# GSM_Link_12_SIM900A.net
KiCad netlist of a schematic drawn in Altium Designer
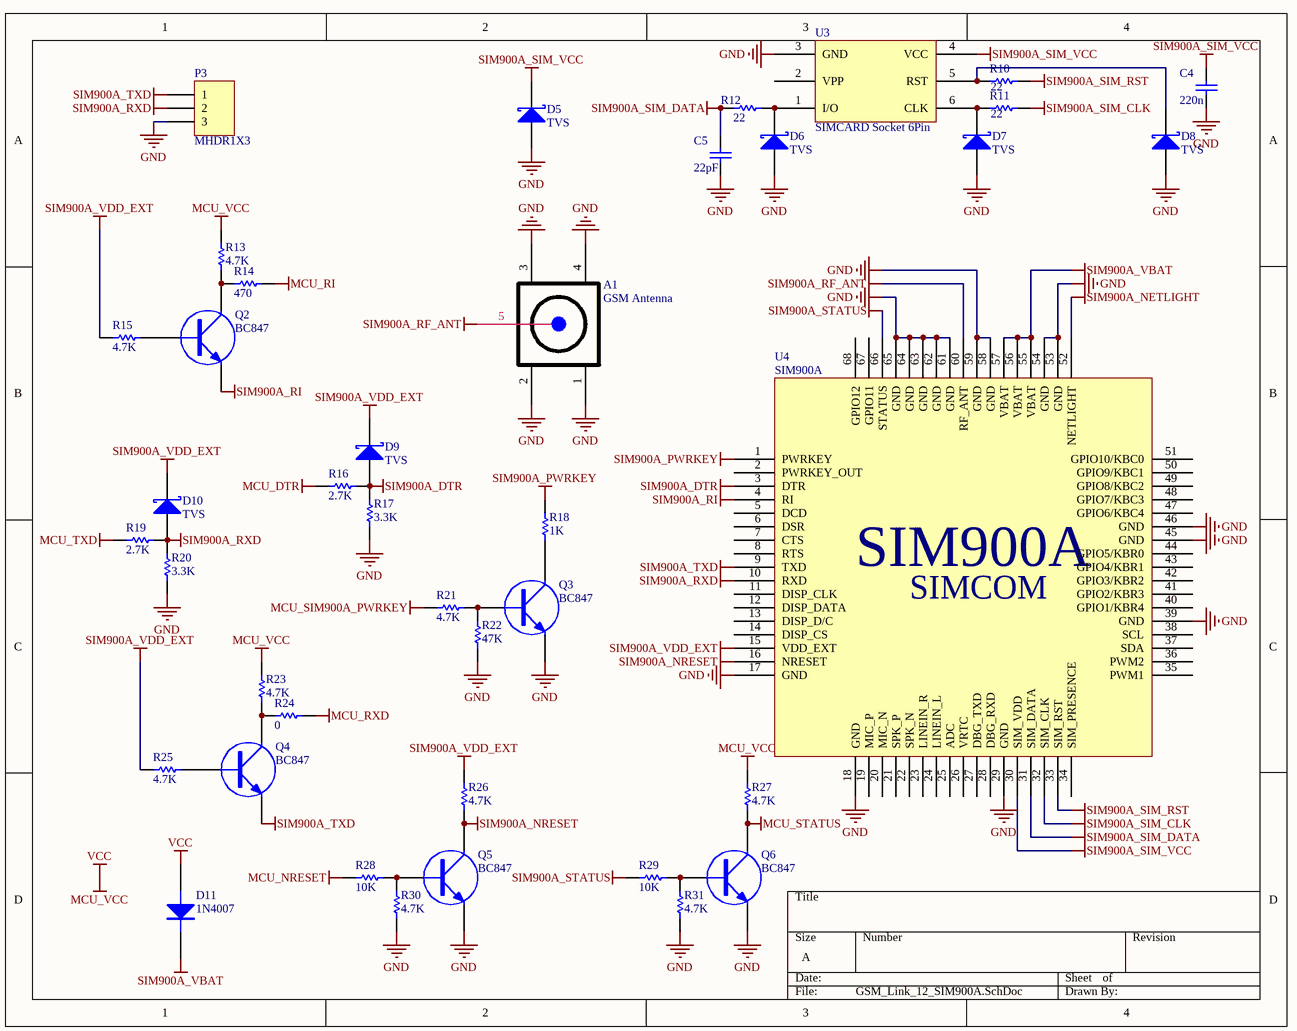
[diagram p0: GSM_Link_12_SIM900A.SchDoc]

(export (version "E")
  (design (tool "Eeschema 10.0.6"))
  (components
    (comp (ref "A1")
      (value "GSM Antenna")
      (footprint "SMA Right Female")
      (libsource (lib "BNB_Altium_LIB_004") (part "SMA KWE-F"))
    )
    (comp (ref "C4")
      (value "220n")
      (footprint "0805_smd")
      (description "Capacitor")
      (fields (field (name "PUBLISHER") "Altium Limited"))
      (libsource (lib "Miscellaneous Devices") (part "Cap"))
    )
    (comp (ref "C5")
      (value "22pF")
      (footprint "0805_smd")
      (description "Capacitor")
      (fields (field (name "PUBLISHER") "Altium Limited"))
      (libsource (lib "Miscellaneous Devices") (part "Cap"))
    )
    (comp (ref "D5")
      (value "TVS")
      (footprint "7227_SMD")
      (description "Schottky Diode")
      (fields (field (name "PUBLISHER") "Altium Limited"))
      (libsource (lib "Miscellaneous Devices") (part "D Schottky"))
    )
    (comp (ref "D6")
      (value "TVS")
      (footprint "7227_SMD")
      (description "Schottky Diode")
      (fields (field (name "PUBLISHER") "Altium Limited"))
      (libsource (lib "Miscellaneous Devices") (part "D Schottky"))
    )
    (comp (ref "D7")
      (value "TVS")
      (footprint "7227_SMD")
      (description "Schottky Diode")
      (fields (field (name "PUBLISHER") "Altium Limited"))
      (libsource (lib "Miscellaneous Devices") (part "D Schottky"))
    )
    (comp (ref "D8")
      (value "TVS")
      (footprint "7227_SMD")
      (description "Schottky Diode")
      (fields (field (name "PUBLISHER") "Altium Limited"))
      (libsource (lib "Miscellaneous Devices") (part "D Schottky"))
    )
    (comp (ref "D9")
      (value "TVS")
      (footprint "7227_SMD")
      (description "Schottky Diode")
      (fields (field (name "PUBLISHER") "Altium Limited"))
      (libsource (lib "Miscellaneous Devices") (part "D Schottky"))
    )
    (comp (ref "D10")
      (value "TVS")
      (footprint "7227_SMD")
      (description "Schottky Diode")
      (fields (field (name "PUBLISHER") "Altium Limited"))
      (libsource (lib "Miscellaneous Devices") (part "D Schottky"))
    )
    (comp (ref "D11")
      (value "1N4007")
      (footprint "7227_SMD")
      (description "Diode")
      (libsource (lib "*") (part "DIODE"))
    )
    (comp (ref "P3")
      (value "MHDR1X3")
      (footprint "CON3_XH")
      (description "Header, 3-Pin")
      (fields (field (name "PUBLISHER") "Altium Limited"))
      (libsource (lib "Miscellaneous Connectors") (part "MHDR1X3"))
    )
    (comp (ref "Q2") (value "BC847") (footprint "SOT23_SMD") (libsource (lib "Schlib75") (part "BC547")))
    (comp (ref "Q3") (value "BC847") (footprint "SOT23_SMD") (libsource (lib "Schlib75") (part "BC547")))
    (comp (ref "Q4") (value "BC847") (footprint "SOT23_SMD") (libsource (lib "Schlib75") (part "BC547")))
    (comp (ref "Q5") (value "BC847") (footprint "SOT23_SMD") (libsource (lib "Schlib75") (part "BC547")))
    (comp (ref "Q6") (value "BC847") (footprint "SOT23_SMD") (libsource (lib "Schlib75") (part "BC547")))
    (comp (ref "R10")
      (value "22")
      (footprint "0805_SMD")
      (description "Resistor")
      (fields (field (name "PUBLISHER") "Altium Limited"))
      (libsource (lib "Miscellaneous Devices") (part "Res1"))
    )
    (comp (ref "R11")
      (value "22")
      (footprint "0805_SMD")
      (description "Resistor")
      (fields (field (name "PUBLISHER") "Altium Limited"))
      (libsource (lib "Miscellaneous Devices") (part "Res1"))
    )
    (comp (ref "R12")
      (value "22")
      (footprint "1206_SMD")
      (description "Resistor")
      (fields (field (name "PUBLISHER") "Altium Limited"))
      (libsource (lib "Miscellaneous Devices") (part "Res1"))
    )
    (comp (ref "R13")
      (value "4.7K")
      (footprint "0805_SMD")
      (description "Resistor")
      (fields (field (name "PUBLISHER") "Altium Limited"))
      (libsource (lib "Miscellaneous Devices") (part "Res1"))
    )
    (comp (ref "R14")
      (value "470")
      (footprint "1206_SMD")
      (description "Resistor")
      (fields (field (name "PUBLISHER") "Altium Limited"))
      (libsource (lib "Miscellaneous Devices") (part "Res1"))
    )
    (comp (ref "R15")
      (value "4.7K")
      (footprint "0805_SMD")
      (description "Resistor")
      (fields (field (name "PUBLISHER") "Altium Limited"))
      (libsource (lib "Miscellaneous Devices") (part "Res1"))
    )
    (comp (ref "R16")
      (value "2.7K")
      (footprint "1206_SMD")
      (description "Resistor")
      (fields (field (name "PUBLISHER") "Altium Limited"))
      (libsource (lib "Miscellaneous Devices") (part "Res1"))
    )
    (comp (ref "R17")
      (value "3.3K")
      (footprint "0805_SMD")
      (description "Resistor")
      (fields (field (name "PUBLISHER") "Altium Limited"))
      (libsource (lib "Miscellaneous Devices") (part "Res1"))
    )
    (comp (ref "R18")
      (value "1K")
      (footprint "0805_SMD")
      (description "Resistor")
      (fields (field (name "PUBLISHER") "Altium Limited"))
      (libsource (lib "Miscellaneous Devices") (part "Res1"))
    )
    (comp (ref "R19")
      (value "2.7K")
      (footprint "1206_SMD")
      (description "Resistor")
      (fields (field (name "PUBLISHER") "Altium Limited"))
      (libsource (lib "Miscellaneous Devices") (part "Res1"))
    )
    (comp (ref "R20")
      (value "3.3K")
      (footprint "1206_SMD")
      (description "Resistor")
      (fields (field (name "PUBLISHER") "Altium Limited"))
      (libsource (lib "Miscellaneous Devices") (part "Res1"))
    )
    (comp (ref "R21")
      (value "4.7K")
      (footprint "0805_SMD")
      (description "Resistor")
      (fields (field (name "PUBLISHER") "Altium Limited"))
      (libsource (lib "Miscellaneous Devices") (part "Res1"))
    )
    (comp (ref "R22")
      (value "47K")
      (footprint "0805_SMD")
      (description "Resistor")
      (fields (field (name "PUBLISHER") "Altium Limited"))
      (libsource (lib "Miscellaneous Devices") (part "Res1"))
    )
    (comp (ref "R23")
      (value "4.7K")
      (footprint "1206_SMD")
      (description "Resistor")
      (fields (field (name "PUBLISHER") "Altium Limited"))
      (libsource (lib "Miscellaneous Devices") (part "Res1"))
    )
    (comp (ref "R24")
      (value "0")
      (footprint "1206_SMD")
      (description "Resistor")
      (fields (field (name "PUBLISHER") "Altium Limited"))
      (libsource (lib "Miscellaneous Devices") (part "Res1"))
    )
    (comp (ref "R25")
      (value "4.7K")
      (footprint "0805_SMD")
      (description "Resistor")
      (fields (field (name "PUBLISHER") "Altium Limited"))
      (libsource (lib "Miscellaneous Devices") (part "Res1"))
    )
    (comp (ref "R26")
      (value "4.7K")
      (footprint "0805_SMD")
      (description "Resistor")
      (fields (field (name "PUBLISHER") "Altium Limited"))
      (libsource (lib "Miscellaneous Devices") (part "Res1"))
    )
    (comp (ref "R27")
      (value "4.7K")
      (footprint "0805_SMD")
      (description "Resistor")
      (fields (field (name "PUBLISHER") "Altium Limited"))
      (libsource (lib "Miscellaneous Devices") (part "Res1"))
    )
    (comp (ref "R28")
      (value "10K")
      (footprint "1206_SMD")
      (description "Resistor")
      (fields (field (name "PUBLISHER") "Altium Limited"))
      (libsource (lib "Miscellaneous Devices") (part "Res1"))
    )
    (comp (ref "R29")
      (value "10K")
      (footprint "0805_SMD")
      (description "Resistor")
      (fields (field (name "PUBLISHER") "Altium Limited"))
      (libsource (lib "Miscellaneous Devices") (part "Res1"))
    )
    (comp (ref "R30")
      (value "4.7K")
      (footprint "0805_SMD")
      (description "Resistor")
      (fields (field (name "PUBLISHER") "Altium Limited"))
      (libsource (lib "Miscellaneous Devices") (part "Res1"))
    )
    (comp (ref "R31")
      (value "4.7K")
      (footprint "0805_SMD")
      (description "Resistor")
      (fields (field (name "PUBLISHER") "Altium Limited"))
      (libsource (lib "Miscellaneous Devices") (part "Res1"))
    )
    (comp (ref "U3")
      (value "SIMCARD Socket 6Pin")
      (footprint "SIMCARD Socket - Ejector")
      (libsource (lib "BNB_Altium_LIB_004") (part "SIM_SOCKET_6PIN"))
    )
    (comp (ref "U4")
      (value "SIM900A")
      (footprint "SIM900A")
      (libsource (lib "BNB_Altium_LIB_003") (part "SIM900A"))
    )
  )
  (nets
    (net (code "1") (name "GND") (class "Default")
      (node (ref "A1") (pin "1") (pintype "passive"))
      (node (ref "A1") (pin "2") (pintype "passive"))
      (node (ref "A1") (pin "3") (pintype "passive"))
      (node (ref "A1") (pin "4") (pintype "passive"))
      (node (ref "C4") (pin "1") (pinfunction "1_1") (pintype "passive"))
      (node (ref "C5") (pin "1") (pinfunction "1_1") (pintype "passive"))
      (node (ref "D5") (pin "A") (pinfunction "A_A") (pintype "passive"))
      (node (ref "D6") (pin "A") (pinfunction "A_A") (pintype "passive"))
      (node (ref "D7") (pin "A") (pinfunction "A_A") (pintype "passive"))
      (node (ref "D8") (pin "A") (pinfunction "A_A") (pintype "passive"))
      (node (ref "P3") (pin "3") (pinfunction "3_3") (pintype "passive"))
      (node (ref "Q3") (pin "2") (pinfunction "E_2") (pintype "passive"))
      (node (ref "Q5") (pin "2") (pinfunction "E_2") (pintype "passive"))
      (node (ref "Q6") (pin "2") (pinfunction "E_2") (pintype "passive"))
      (node (ref "R17") (pin "1") (pinfunction "1_1") (pintype "passive"))
      (node (ref "R20") (pin "1") (pinfunction "1_1") (pintype "passive"))
      (node (ref "R22") (pin "2") (pinfunction "2_2") (pintype "passive"))
      (node (ref "R30") (pin "1") (pinfunction "1_1") (pintype "passive"))
      (node (ref "R31") (pin "1") (pinfunction "1_1") (pintype "passive"))
      (node (ref "U3") (pin "3") (pinfunction "GND_3") (pintype "passive"))
      (node (ref "U4") (pin "17") (pinfunction "GND_17") (pintype "passive"))
      (node (ref "U4") (pin "18") (pinfunction "GND_18") (pintype "passive"))
      (node (ref "U4") (pin "29") (pinfunction "GND_29") (pintype "passive"))
      (node (ref "U4") (pin "39") (pinfunction "GND_39") (pintype "passive"))
      (node (ref "U4") (pin "45") (pinfunction "GND_45") (pintype "passive"))
      (node (ref "U4") (pin "46") (pinfunction "GND_46") (pintype "passive"))
      (node (ref "U4") (pin "53") (pinfunction "GND_53") (pintype "passive"))
      (node (ref "U4") (pin "54") (pinfunction "GND_54") (pintype "passive"))
      (node (ref "U4") (pin "58") (pinfunction "GND_58") (pintype "passive"))
      (node (ref "U4") (pin "59") (pinfunction "GND_59") (pintype "passive"))
      (node (ref "U4") (pin "61") (pinfunction "GND_61") (pintype "passive"))
      (node (ref "U4") (pin "62") (pinfunction "GND_62") (pintype "passive"))
      (node (ref "U4") (pin "63") (pinfunction "GND_63") (pintype "passive"))
      (node (ref "U4") (pin "64") (pinfunction "GND_64") (pintype "passive"))
      (node (ref "U4") (pin "65") (pinfunction "GND_65") (pintype "passive"))
    )
    (net (code "2") (name "MCU_DTR") (class "Default")
      (node (ref "R16") (pin "2") (pinfunction "2_2") (pintype "passive"))
    )
    (net (code "3") (name "MCU_NRESET") (class "Default")
      (node (ref "R28") (pin "1") (pinfunction "1_1") (pintype "passive"))
    )
    (net (code "4") (name "MCU_RI") (class "Default")
      (node (ref "R14") (pin "2") (pinfunction "2_2") (pintype "passive"))
    )
    (net (code "5") (name "MCU_RXD") (class "Default")
      (node (ref "R24") (pin "2") (pinfunction "2_2") (pintype "passive"))
    )
    (net (code "6") (name "MCU_SIM900A_PWRKEY") (class "Default")
      (node (ref "R21") (pin "1") (pinfunction "1_1") (pintype "passive"))
    )
    (net (code "7") (name "MCU_STATUS") (class "Default")
      (node (ref "Q6") (pin "3") (pinfunction "C_3") (pintype "passive"))
      (node (ref "R27") (pin "2") (pinfunction "2_2") (pintype "passive"))
    )
    (net (code "8") (name "MCU_TXD") (class "Default")
      (node (ref "R19") (pin "2") (pinfunction "2_2") (pintype "passive"))
    )
    (net (code "9") (name "MCU_VCC") (class "Default")
      (node (ref "D11") (pin "A") (pinfunction "1_A") (pintype "passive"))
      (node (ref "R13") (pin "2") (pinfunction "2_2") (pintype "passive"))
      (node (ref "R23") (pin "2") (pinfunction "2_2") (pintype "passive"))
      (node (ref "R27") (pin "1") (pinfunction "1_1") (pintype "passive"))
    )
    (net (code "10") (name "Net-(Q2-B)") (class "Default")
      (node (ref "Q2") (pin "1") (pinfunction "B_1") (pintype "passive"))
      (node (ref "R15") (pin "2") (pinfunction "2_2") (pintype "passive"))
    )
    (net (code "11") (name "Net-(Q2-C)") (class "Default")
      (node (ref "Q2") (pin "3") (pinfunction "C_3") (pintype "passive"))
      (node (ref "R13") (pin "1") (pinfunction "1_1") (pintype "passive"))
      (node (ref "R14") (pin "1") (pinfunction "1_1") (pintype "passive"))
    )
    (net (code "12") (name "Net-(Q3-B)") (class "Default")
      (node (ref "Q3") (pin "1") (pinfunction "B_1") (pintype "passive"))
      (node (ref "R21") (pin "2") (pinfunction "2_2") (pintype "passive"))
      (node (ref "R22") (pin "1") (pinfunction "1_1") (pintype "passive"))
    )
    (net (code "13") (name "Net-(Q3-C)") (class "Default")
      (node (ref "Q3") (pin "3") (pinfunction "C_3") (pintype "passive"))
      (node (ref "R18") (pin "1") (pinfunction "1_1") (pintype "passive"))
    )
    (net (code "14") (name "Net-(Q4-B)") (class "Default")
      (node (ref "Q4") (pin "1") (pinfunction "B_1") (pintype "passive"))
      (node (ref "R25") (pin "2") (pinfunction "2_2") (pintype "passive"))
    )
    (net (code "15") (name "Net-(Q4-C)") (class "Default")
      (node (ref "Q4") (pin "3") (pinfunction "C_3") (pintype "passive"))
      (node (ref "R23") (pin "1") (pinfunction "1_1") (pintype "passive"))
      (node (ref "R24") (pin "1") (pinfunction "1_1") (pintype "passive"))
    )
    (net (code "16") (name "Net-(Q5-B)") (class "Default")
      (node (ref "Q5") (pin "1") (pinfunction "B_1") (pintype "passive"))
      (node (ref "R28") (pin "2") (pinfunction "2_2") (pintype "passive"))
      (node (ref "R30") (pin "2") (pinfunction "2_2") (pintype "passive"))
    )
    (net (code "17") (name "Net-(Q6-B)") (class "Default")
      (node (ref "Q6") (pin "1") (pinfunction "B_1") (pintype "passive"))
      (node (ref "R29") (pin "1") (pinfunction "1_1") (pintype "passive"))
      (node (ref "R31") (pin "2") (pinfunction "2_2") (pintype "passive"))
    )
    (net (code "18") (name "Net-(U3-CLK)") (class "Default")
      (node (ref "D7") (pin "K") (pinfunction "K_K") (pintype "passive"))
      (node (ref "R11") (pin "1") (pinfunction "1_1") (pintype "passive"))
      (node (ref "U3") (pin "6") (pinfunction "CLK_6") (pintype "passive"))
    )
    (net (code "19") (name "Net-(U3-I{slash}O)") (class "Default")
      (node (ref "D6") (pin "K") (pinfunction "K_K") (pintype "passive"))
      (node (ref "R12") (pin "1") (pinfunction "1_1") (pintype "passive"))
      (node (ref "U3") (pin "1") (pinfunction "I/O_1") (pintype "passive"))
    )
    (net (code "20") (name "Net-(U3-RST)") (class "Default")
      (node (ref "D8") (pin "K") (pinfunction "K_K") (pintype "passive"))
      (node (ref "R10") (pin "1") (pinfunction "1_1") (pintype "passive"))
      (node (ref "U3") (pin "5") (pinfunction "RST_5") (pintype "passive"))
    )
    (net (code "21") (name "SIM900A_DTR") (class "Default")
      (node (ref "D9") (pin "A") (pinfunction "A_A") (pintype "passive"))
      (node (ref "R16") (pin "1") (pinfunction "1_1") (pintype "passive"))
      (node (ref "R17") (pin "2") (pinfunction "2_2") (pintype "passive"))
      (node (ref "U4") (pin "3") (pinfunction "DTR_3") (pintype "passive"))
    )
    (net (code "22") (name "SIM900A_NETLIGHT") (class "Default")
      (node (ref "U4") (pin "52") (pinfunction "NETLIGHT_52") (pintype "passive"))
    )
    (net (code "23") (name "SIM900A_NRESET") (class "Default")
      (node (ref "Q5") (pin "3") (pinfunction "C_3") (pintype "passive"))
      (node (ref "R26") (pin "1") (pinfunction "1_1") (pintype "passive"))
      (node (ref "U4") (pin "16") (pinfunction "NRESET_16") (pintype "passive"))
    )
    (net (code "24") (name "SIM900A_PWRKEY") (class "Default")
      (node (ref "R18") (pin "2") (pinfunction "2_2") (pintype "passive"))
      (node (ref "U4") (pin "1") (pinfunction "PWRKEY_1") (pintype "passive"))
    )
    (net (code "25") (name "SIM900A_RF_ANT") (class "Default")
      (node (ref "A1") (pin "5") (pintype "passive"))
      (node (ref "U4") (pin "60") (pinfunction "RF_ANT_60") (pintype "passive"))
    )
    (net (code "26") (name "SIM900A_RI") (class "Default")
      (node (ref "Q2") (pin "2") (pinfunction "E_2") (pintype "passive"))
      (node (ref "U4") (pin "4") (pinfunction "RI_4") (pintype "passive"))
    )
    (net (code "27") (name "SIM900A_RXD") (class "Default")
      (node (ref "D10") (pin "A") (pinfunction "A_A") (pintype "passive"))
      (node (ref "P3") (pin "2") (pinfunction "2_2") (pintype "passive"))
      (node (ref "R19") (pin "1") (pinfunction "1_1") (pintype "passive"))
      (node (ref "R20") (pin "2") (pinfunction "2_2") (pintype "passive"))
      (node (ref "U4") (pin "10") (pinfunction "RXD_10") (pintype "passive"))
    )
    (net (code "28") (name "SIM900A_SIM_CLK") (class "Default")
      (node (ref "R11") (pin "2") (pinfunction "2_2") (pintype "passive"))
      (node (ref "U4") (pin "32") (pinfunction "SIM_CLK_32") (pintype "passive"))
    )
    (net (code "29") (name "SIM900A_SIM_DATA") (class "Default")
      (node (ref "C5") (pin "2") (pinfunction "2_2") (pintype "passive"))
      (node (ref "R12") (pin "2") (pinfunction "2_2") (pintype "passive"))
      (node (ref "U4") (pin "31") (pinfunction "SIM_DATA_31") (pintype "passive"))
    )
    (net (code "30") (name "SIM900A_SIM_RST") (class "Default")
      (node (ref "R10") (pin "2") (pinfunction "2_2") (pintype "passive"))
      (node (ref "U4") (pin "33") (pinfunction "SIM_RST_33") (pintype "passive"))
    )
    (net (code "31") (name "SIM900A_SIM_VCC") (class "Default")
      (node (ref "C4") (pin "2") (pinfunction "2_2") (pintype "passive"))
      (node (ref "D5") (pin "K") (pinfunction "K_K") (pintype "passive"))
      (node (ref "U3") (pin "4") (pinfunction "VCC_4") (pintype "passive"))
      (node (ref "U4") (pin "30") (pinfunction "SIM_VDD_30") (pintype "passive"))
    )
    (net (code "32") (name "SIM900A_STATUS") (class "Default")
      (node (ref "R29") (pin "2") (pinfunction "2_2") (pintype "passive"))
      (node (ref "U4") (pin "66") (pinfunction "STATUS_66") (pintype "passive"))
    )
    (net (code "33") (name "SIM900A_TXD") (class "Default")
      (node (ref "P3") (pin "1") (pinfunction "1_1") (pintype "passive"))
      (node (ref "Q4") (pin "2") (pinfunction "E_2") (pintype "passive"))
      (node (ref "U4") (pin "9") (pinfunction "TXD_9") (pintype "passive"))
    )
    (net (code "34") (name "SIM900A_VBAT") (class "Default")
      (node (ref "D11") (pin "K") (pinfunction "2_K") (pintype "passive"))
      (node (ref "U4") (pin "55") (pinfunction "VBAT_55") (pintype "passive"))
      (node (ref "U4") (pin "56") (pinfunction "VBAT_56") (pintype "passive"))
      (node (ref "U4") (pin "57") (pinfunction "VBAT_57") (pintype "passive"))
    )
    (net (code "35") (name "SIM900A_VDD_EXT") (class "Default")
      (node (ref "D10") (pin "K") (pinfunction "K_K") (pintype "passive"))
      (node (ref "D9") (pin "K") (pinfunction "K_K") (pintype "passive"))
      (node (ref "R15") (pin "1") (pinfunction "1_1") (pintype "passive"))
      (node (ref "R25") (pin "1") (pinfunction "1_1") (pintype "passive"))
      (node (ref "R26") (pin "2") (pinfunction "2_2") (pintype "passive"))
      (node (ref "U4") (pin "15") (pinfunction "VDD_EXT_15") (pintype "passive"))
    )
    (net (code "36") (name "unconnected-(U3-VPP-Pad2)") (class "Default")
      (node (ref "U3") (pin "2") (pinfunction "VPP_2") (pintype "passive"))
    )
    (net (code "37") (name "unconnected-(U4-ADC-Pad25)") (class "Default")
      (node (ref "U4") (pin "25") (pinfunction "ADC_25") (pintype "passive"))
    )
    (net (code "38") (name "unconnected-(U4-CTS-Pad7)") (class "Default")
      (node (ref "U4") (pin "7") (pinfunction "CTS_7") (pintype "passive"))
    )
    (net (code "39") (name "unconnected-(U4-DBG_RXD-Pad28)") (class "Default")
      (node (ref "U4") (pin "28") (pinfunction "DBG_RXD_28") (pintype "passive"))
    )
    (net (code "40") (name "unconnected-(U4-DBG_TXD-Pad27)") (class "Default")
      (node (ref "U4") (pin "27") (pinfunction "DBG_TXD_27") (pintype "passive"))
    )
    (net (code "41") (name "unconnected-(U4-DCD-Pad5)") (class "Default")
      (node (ref "U4") (pin "5") (pinfunction "DCD_5") (pintype "passive"))
    )
    (net (code "42") (name "unconnected-(U4-DISP_CLK-Pad11)") (class "Default")
      (node (ref "U4") (pin "11") (pinfunction "DISP_CLK_11") (pintype "passive"))
    )
    (net (code "43") (name "unconnected-(U4-DISP_CS-Pad14)") (class "Default")
      (node (ref "U4") (pin "14") (pinfunction "DISP_CS_14") (pintype "passive"))
    )
    (net (code "44") (name "unconnected-(U4-DISP_DATA-Pad12)") (class "Default")
      (node (ref "U4") (pin "12") (pinfunction "DISP_DATA_12") (pintype "passive"))
    )
    (net (code "45") (name "unconnected-(U4-DISP_D{slash}C-Pad13)") (class "Default")
      (node (ref "U4") (pin "13") (pinfunction "DISP_D/C_13") (pintype "passive"))
    )
    (net (code "46") (name "unconnected-(U4-DSR-Pad6)") (class "Default")
      (node (ref "U4") (pin "6") (pinfunction "DSR_6") (pintype "passive"))
    )
    (net (code "47") (name "unconnected-(U4-GPIO1{slash}KBR4-Pad40)") (class "Default")
      (node (ref "U4") (pin "40") (pinfunction "GPIO1/KBR4_40") (pintype "passive"))
    )
    (net (code "48") (name "unconnected-(U4-GPIO2{slash}KBR3-Pad41)") (class "Default")
      (node (ref "U4") (pin "41") (pinfunction "GPIO2/KBR3_41") (pintype "passive"))
    )
    (net (code "49") (name "unconnected-(U4-GPIO3{slash}KBR2-Pad42)") (class "Default")
      (node (ref "U4") (pin "42") (pinfunction "GPIO3/KBR2_42") (pintype "passive"))
    )
    (net (code "50") (name "unconnected-(U4-GPIO4{slash}KBR1-Pad43)") (class "Default")
      (node (ref "U4") (pin "43") (pinfunction "GPIO4/KBR1_43") (pintype "passive"))
    )
    (net (code "51") (name "unconnected-(U4-GPIO5{slash}KBR0-Pad44)") (class "Default")
      (node (ref "U4") (pin "44") (pinfunction "GPIO5/KBR0_44") (pintype "passive"))
    )
    (net (code "52") (name "unconnected-(U4-GPIO6{slash}KBC4-Pad47)") (class "Default")
      (node (ref "U4") (pin "47") (pinfunction "GPIO6/KBC4_47") (pintype "passive"))
    )
    (net (code "53") (name "unconnected-(U4-GPIO7{slash}KBC3-Pad48)") (class "Default")
      (node (ref "U4") (pin "48") (pinfunction "GPIO7/KBC3_48") (pintype "passive"))
    )
    (net (code "54") (name "unconnected-(U4-GPIO8{slash}KBC2-Pad49)") (class "Default")
      (node (ref "U4") (pin "49") (pinfunction "GPIO8/KBC2_49") (pintype "passive"))
    )
    (net (code "55") (name "unconnected-(U4-GPIO9{slash}KBC1-Pad50)") (class "Default")
      (node (ref "U4") (pin "50") (pinfunction "GPIO9/KBC1_50") (pintype "passive"))
    )
    (net (code "56") (name "unconnected-(U4-GPIO10{slash}KBC0-Pad51)") (class "Default")
      (node (ref "U4") (pin "51") (pinfunction "GPIO10/KBC0_51") (pintype "passive"))
    )
    (net (code "57") (name "unconnected-(U4-GPIO11-Pad67)") (class "Default")
      (node (ref "U4") (pin "67") (pinfunction "GPIO11_67") (pintype "passive"))
    )
    (net (code "58") (name "unconnected-(U4-GPIO12-Pad68)") (class "Default")
      (node (ref "U4") (pin "68") (pinfunction "GPIO12_68") (pintype "passive"))
    )
    (net (code "59") (name "unconnected-(U4-LINEIN_L-Pad24)") (class "Default")
      (node (ref "U4") (pin "24") (pinfunction "LINEIN_L_24") (pintype "passive"))
    )
    (net (code "60") (name "unconnected-(U4-LINEIN_R-Pad23)") (class "Default")
      (node (ref "U4") (pin "23") (pinfunction "LINEIN_R_23") (pintype "passive"))
    )
    (net (code "61") (name "unconnected-(U4-MIC_N-Pad20)") (class "Default")
      (node (ref "U4") (pin "20") (pinfunction "MIC_N_20") (pintype "passive"))
    )
    (net (code "62") (name "unconnected-(U4-MIC_P-Pad19)") (class "Default")
      (node (ref "U4") (pin "19") (pinfunction "MIC_P_19") (pintype "passive"))
    )
    (net (code "63") (name "unconnected-(U4-PWM1-Pad35)") (class "Default")
      (node (ref "U4") (pin "35") (pinfunction "PWM1_35") (pintype "passive"))
    )
    (net (code "64") (name "unconnected-(U4-PWM2-Pad36)") (class "Default")
      (node (ref "U4") (pin "36") (pinfunction "PWM2_36") (pintype "passive"))
    )
    (net (code "65") (name "unconnected-(U4-PWRKEY_OUT-Pad2)") (class "Default")
      (node (ref "U4") (pin "2") (pinfunction "PWRKEY_OUT_2") (pintype "passive"))
    )
    (net (code "66") (name "unconnected-(U4-RTS-Pad8)") (class "Default")
      (node (ref "U4") (pin "8") (pinfunction "RTS_8") (pintype "passive"))
    )
    (net (code "67") (name "unconnected-(U4-SCL-Pad38)") (class "Default")
      (node (ref "U4") (pin "38") (pinfunction "SCL_38") (pintype "passive"))
    )
    (net (code "68") (name "unconnected-(U4-SDA-Pad37)") (class "Default")
      (node (ref "U4") (pin "37") (pinfunction "SDA_37") (pintype "passive"))
    )
    (net (code "69") (name "unconnected-(U4-SIM_PRESENCE-Pad34)") (class "Default")
      (node (ref "U4") (pin "34") (pinfunction "SIM_PRESENCE_34") (pintype "passive"))
    )
    (net (code "70") (name "unconnected-(U4-SPK_N-Pad22)") (class "Default")
      (node (ref "U4") (pin "22") (pinfunction "SPK_N_22") (pintype "passive"))
    )
    (net (code "71") (name "unconnected-(U4-SPK_P-Pad21)") (class "Default")
      (node (ref "U4") (pin "21") (pinfunction "SPK_P_21") (pintype "passive"))
    )
    (net (code "72") (name "unconnected-(U4-VRTC-Pad26)") (class "Default")
      (node (ref "U4") (pin "26") (pinfunction "VRTC_26") (pintype "passive"))
    )
  )
)
